# SparkFun_Qwiic_CO2_Sensor_XENSIV_PAS.net
KiCad netlist of a schematic drawn in EAGLE
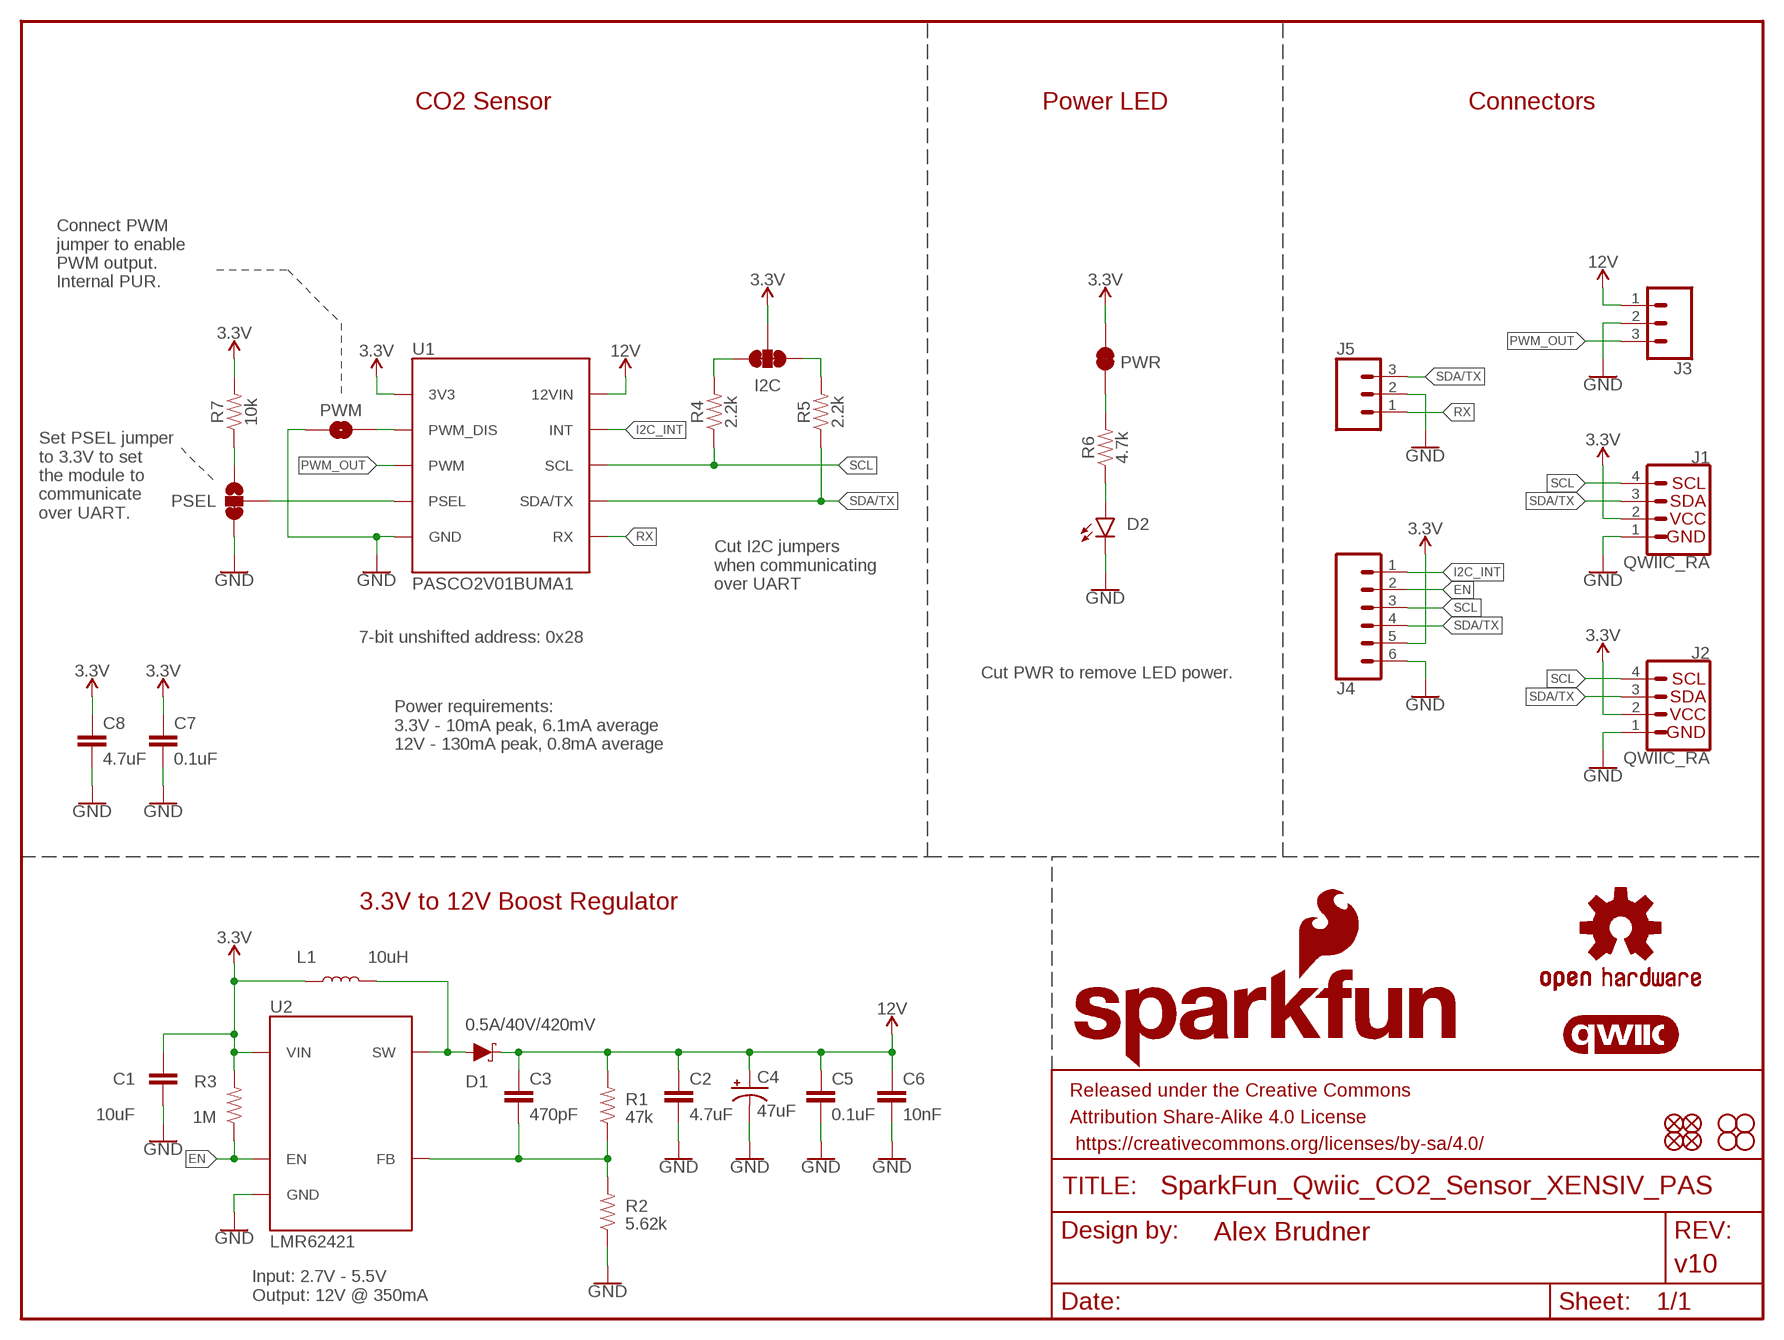
[diagram p0: schematic, sheet 1]

(export (version "E")
  (design (tool "Eeschema 10.0.6"))
  (components
    (comp (ref "C1")
      (value "10uF")
      (footprint "eagle-import:0805")
      (libsource (lib "eagle-import") (part "10UF-0805-25V-10%"))
    )
    (comp (ref "C2")
      (value "4.7uF")
      (footprint "eagle-import:0603")
      (libsource (lib "eagle-import") (part "4.7UF-0603-35V-(20%)"))
    )
    (comp (ref "C3")
      (value "470pF")
      (footprint "eagle-import:0603")
      (libsource (lib "eagle-import") (part "470PF-0603-50V-5%"))
    )
    (comp (ref "C4")
      (value "47uF")
      (footprint "eagle-import:PANASONIC_D")
      (libsource (lib "eagle-import") (part "47UF-POLAR-PANASONIC_D-35V-20%"))
    )
    (comp (ref "C5")
      (value "0.1uF")
      (footprint "eagle-import:0603")
      (libsource (lib "eagle-import") (part "0.1UF-0603-25V-5%"))
    )
    (comp (ref "C6")
      (value "10nF")
      (footprint "eagle-import:0603")
      (libsource (lib "eagle-import") (part "10NF-0603-50V-10%"))
    )
    (comp (ref "C7")
      (value "0.1uF")
      (footprint "eagle-import:0603")
      (libsource (lib "eagle-import") (part "0.1UF-0603-25V-5%"))
    )
    (comp (ref "C8")
      (value "4.7uF")
      (footprint "eagle-import:0603")
      (libsource (lib "eagle-import") (part "4.7UF-0603-35V-(20%)"))
    )
    (comp (ref "D1")
      (value "0.5A/40V/420mV")
      (footprint "eagle-import:SOD-323")
      (libsource (lib "eagle-import") (part "DIODE-SCHOTTKY-PMEG4005EJ"))
    )
    (comp (ref "D2")
      (value "LED-RED_0603-KB")
      (footprint "eagle-import:LED-0603")
      (libsource (lib "eagle-import") (part "LED-RED_0603-KB"))
    )
    (comp (ref "FD1")
      (value "FIDUCIALUFIDUCIAL")
      (footprint "eagle-import:FIDUCIAL-MICRO")
      (libsource (lib "eagle-import") (part "FIDUCIALUFIDUCIAL"))
    )
    (comp (ref "FD2")
      (value "FIDUCIALUFIDUCIAL")
      (footprint "eagle-import:FIDUCIAL-MICRO")
      (libsource (lib "eagle-import") (part "FIDUCIALUFIDUCIAL"))
    )
    (comp (ref "FD3")
      (value "FIDUCIALUFIDUCIAL")
      (footprint "eagle-import:FIDUCIAL-MICRO")
      (libsource (lib "eagle-import") (part "FIDUCIALUFIDUCIAL"))
    )
    (comp (ref "FD4")
      (value "FIDUCIALUFIDUCIAL")
      (footprint "eagle-import:FIDUCIAL-MICRO")
      (libsource (lib "eagle-import") (part "FIDUCIALUFIDUCIAL"))
    )
    (comp (ref "FRAME1")
      (value "FRAME-LETTER")
      (footprint "eagle-import:CREATIVE_COMMONS")
      (fields (field (name "DESIGNER") "Alex Brudner") (field (name "REV") "v10"))
      (libsource (lib "eagle-import") (part "FRAME-LETTER"))
    )
    (comp (ref "H1")
      (value "STAND-OFF")
      (footprint "eagle-import:STAND-OFF")
      (libsource (lib "eagle-import") (part "STAND-OFF"))
    )
    (comp (ref "H2")
      (value "STAND-OFF")
      (footprint "eagle-import:STAND-OFF")
      (libsource (lib "eagle-import") (part "STAND-OFF"))
    )
    (comp (ref "H3")
      (value "STAND-OFF")
      (footprint "eagle-import:STAND-OFF")
      (libsource (lib "eagle-import") (part "STAND-OFF"))
    )
    (comp (ref "H4")
      (value "STAND-OFF")
      (footprint "eagle-import:STAND-OFF")
      (libsource (lib "eagle-import") (part "STAND-OFF"))
    )
    (comp (ref "I2C")
      (value "JUMPER-SMT_3_2-NC_TRACE_SILK")
      (footprint "eagle-import:SMT-JUMPER_3_2-NC_TRACE_SILK")
      (libsource (lib "eagle-import") (part "JUMPER-SMT_3_2-NC_TRACE_SILK"))
    )
    (comp (ref "J1")
      (value "QWIIC_RA")
      (footprint "eagle-import:JST04_1MM_RA")
      (libsource (lib "eagle-import") (part "QWIIC_CONNECTORJS-1MM"))
    )
    (comp (ref "J2")
      (value "QWIIC_RA")
      (footprint "eagle-import:JST04_1MM_RA")
      (libsource (lib "eagle-import") (part "QWIIC_CONNECTORJS-1MM"))
    )
    (comp (ref "J3")
      (value "CONN_031X03_NO_SILK")
      (footprint "eagle-import:1X03_NO_SILK")
      (libsource (lib "eagle-import") (part "CONN_031X03_NO_SILK"))
    )
    (comp (ref "J4")
      (value "CONN_06NO_SILK_NO_POP")
      (footprint "eagle-import:1X06_NO_SILK")
      (libsource (lib "eagle-import") (part "CONN_06NO_SILK_NO_POP"))
    )
    (comp (ref "J5")
      (value "CONN_031X03_NO_SILK")
      (footprint "eagle-import:1X03_NO_SILK")
      (libsource (lib "eagle-import") (part "CONN_031X03_NO_SILK"))
    )
    (comp (ref "L1")
      (value "10uH")
      (footprint "eagle-import:0805")
      (libsource (lib "eagle-import") (part "10UH"))
    )
    (comp (ref "LOGO1")
      (value "SFE_LOGO_NAME_FLAME.1_INCH")
      (footprint "eagle-import:SFE_LOGO_NAME_FLAME_.1")
      (libsource (lib "eagle-import") (part "SFE_LOGO_NAME_FLAME.1_INCH"))
    )
    (comp (ref "LOGO2")
      (value "QWIIC_LOGO_5MM")
      (footprint "eagle-import:QWIIC_5MM")
      (libsource (lib "eagle-import") (part "QWIIC_LOGO_5MM"))
    )
    (comp (ref "LOGO3")
      (value "OSHW-LOGOMINI")
      (footprint "eagle-import:OSHW-LOGO-MINI")
      (libsource (lib "eagle-import") (part "OSHW-LOGOMINI"))
    )
    (comp (ref "PSEL")
      (value "JUMPER-SMT_3_1-NC_TRACE_SILK")
      (footprint "eagle-import:SMT-JUMPER_3_1-NC_TRACE_SILK")
      (libsource (lib "eagle-import") (part "JUMPER-SMT_3_1-NC_TRACE_SILK"))
    )
    (comp (ref "PWM")
      (value "JUMPER-SMT_2_NO_SILK")
      (footprint "eagle-import:SMT-JUMPER_2_NO_SILK")
      (libsource (lib "eagle-import") (part "JUMPER-SMT_2_NO_SILK"))
    )
    (comp (ref "PWR")
      (value "JUMPER-SMT_2_NC_TRACE_SILK")
      (footprint "eagle-import:SMT-JUMPER_2_NC_TRACE_SILK")
      (libsource (lib "eagle-import") (part "JUMPER-SMT_2_NC_TRACE_SILK"))
    )
    (comp (ref "R1")
      (value "47k")
      (footprint "eagle-import:0603")
      (libsource (lib "eagle-import") (part "47KOHM-0603-1/10W-1%"))
    )
    (comp (ref "R2")
      (value "5.62k")
      (footprint "eagle-import:0603")
      (libsource (lib "eagle-import") (part "5.62KOHM-0603-1/10W-1%"))
    )
    (comp (ref "R3")
      (value "1M")
      (footprint "eagle-import:0603")
      (libsource (lib "eagle-import") (part "1MOHM-0603-1/4W-5%"))
    )
    (comp (ref "R4")
      (value "2.2k")
      (footprint "eagle-import:0603")
      (libsource (lib "eagle-import") (part "2.2KOHM-0603-1/10W-1%"))
    )
    (comp (ref "R5")
      (value "2.2k")
      (footprint "eagle-import:0603")
      (libsource (lib "eagle-import") (part "2.2KOHM-0603-1/10W-1%"))
    )
    (comp (ref "R6")
      (value "4.7k")
      (footprint "eagle-import:0603")
      (libsource (lib "eagle-import") (part "4.7KOHM-0603-1/10W-1%"))
    )
    (comp (ref "R7")
      (value "10k")
      (footprint "eagle-import:0603")
      (libsource (lib "eagle-import") (part "10KOHM-0603-1/10W-1%"))
    )
    (comp (ref "U1")
      (value "PASCO2V01BUMA1")
      (footprint "eagle-import:LG-MLGA-14-1_Z8B00206105")
      (libsource (lib "eagle-import") (part "PASCO2V01"))
    )
    (comp (ref "U2")
      (value "LMR62421")
      (footprint "eagle-import:SOT95P280X145-5M")
      (libsource (lib "eagle-import") (part "LMR62421"))
    )
  )
  (nets
    (net (code "1") (name "3.3V") (class "Default")
      (node (ref "C1") (pin "1") (pinfunction "1_1") (pintype "passive"))
      (node (ref "C7") (pin "1") (pinfunction "1_1") (pintype "passive"))
      (node (ref "C8") (pin "1") (pinfunction "1_1") (pintype "passive"))
      (node (ref "I2C") (pin "2") (pinfunction "2_2") (pintype "passive"))
      (node (ref "J1") (pin "2") (pinfunction "2_2") (pintype "power_in"))
      (node (ref "J2") (pin "2") (pinfunction "2_2") (pintype "power_in"))
      (node (ref "J4") (pin "5") (pinfunction "5_5") (pintype "passive"))
      (node (ref "L1") (pin "1") (pinfunction "1_1") (pintype "passive"))
      (node (ref "PWR") (pin "2") (pinfunction "2_2") (pintype "passive"))
      (node (ref "R3") (pin "2") (pinfunction "2_2") (pintype "passive"))
      (node (ref "R7") (pin "2") (pinfunction "2_2") (pintype "passive"))
      (node (ref "U1") (pin "1") (pinfunction "3V3_1") (pintype "bidirectional"))
      (node (ref "U2") (pin "5") (pinfunction "VIN_5") (pintype "bidirectional"))
    )
    (net (code "2") (name "12V") (class "Default")
      (node (ref "C2") (pin "1") (pinfunction "1_1") (pintype "passive"))
      (node (ref "C3") (pin "1") (pinfunction "1_1") (pintype "passive"))
      (node (ref "C4") (pin "+") (pinfunction "+_+") (pintype "passive"))
      (node (ref "C5") (pin "1") (pinfunction "1_1") (pintype "passive"))
      (node (ref "C6") (pin "1") (pinfunction "1_1") (pintype "passive"))
      (node (ref "D1") (pin "C") (pinfunction "C_C") (pintype "passive"))
      (node (ref "J3") (pin "1") (pinfunction "1_1") (pintype "passive"))
      (node (ref "R1") (pin "2") (pinfunction "2_2") (pintype "passive"))
      (node (ref "U1") (pin "10") (pinfunction "12VIN_10") (pintype "bidirectional"))
    )
    (net (code "3") (name "EN") (class "Default")
      (node (ref "J4") (pin "2") (pinfunction "2_2") (pintype "passive"))
      (node (ref "R3") (pin "1") (pinfunction "1_1") (pintype "passive"))
      (node (ref "U2") (pin "4") (pinfunction "EN_4") (pintype "bidirectional"))
    )
    (net (code "4") (name "GND") (class "Default")
      (node (ref "C1") (pin "2") (pinfunction "2_2") (pintype "passive"))
      (node (ref "C2") (pin "2") (pinfunction "2_2") (pintype "passive"))
      (node (ref "C4") (pin "-") (pinfunction "-_-") (pintype "passive"))
      (node (ref "C5") (pin "2") (pinfunction "2_2") (pintype "passive"))
      (node (ref "C6") (pin "2") (pinfunction "2_2") (pintype "passive"))
      (node (ref "C7") (pin "2") (pinfunction "2_2") (pintype "passive"))
      (node (ref "C8") (pin "2") (pinfunction "2_2") (pintype "passive"))
      (node (ref "D2") (pin "C") (pinfunction "C_C") (pintype "passive"))
      (node (ref "J1") (pin "1") (pinfunction "1_1") (pintype "power_in"))
      (node (ref "J2") (pin "1") (pinfunction "1_1") (pintype "power_in"))
      (node (ref "J3") (pin "2") (pinfunction "2_2") (pintype "passive"))
      (node (ref "J4") (pin "6") (pinfunction "6_6") (pintype "passive"))
      (node (ref "J5") (pin "2") (pinfunction "2_2") (pintype "passive"))
      (node (ref "PSEL") (pin "3") (pinfunction "3_3") (pintype "passive"))
      (node (ref "PWM") (pin "1") (pinfunction "1_1") (pintype "passive"))
      (node (ref "R2") (pin "1") (pinfunction "1_1") (pintype "passive"))
      (node (ref "U1") (pin "11") (pinfunction "GND_11") (pintype "bidirectional"))
      (node (ref "U1") (pin "12") (pinfunction "GND_12") (pintype "bidirectional"))
      (node (ref "U1") (pin "13") (pinfunction "GND_13") (pintype "bidirectional"))
      (node (ref "U1") (pin "14") (pinfunction "GND_14") (pintype "bidirectional"))
      (node (ref "U1") (pin "6") (pinfunction "GND_6") (pintype "bidirectional"))
      (node (ref "U2") (pin "2") (pinfunction "GND_2") (pintype "bidirectional"))
    )
    (net (code "5") (name "I2C_INT") (class "Default")
      (node (ref "J4") (pin "1") (pinfunction "1_1") (pintype "passive"))
      (node (ref "U1") (pin "7") (pinfunction "INT_7") (pintype "bidirectional"))
    )
    (net (code "6") (name "Net-(D2-PadA)") (class "Default")
      (node (ref "D2") (pin "A") (pinfunction "A_A") (pintype "passive"))
      (node (ref "R6") (pin "1") (pinfunction "1_1") (pintype "passive"))
    )
    (net (code "7") (name "Net-(I2C-Pad1)") (class "Default")
      (node (ref "I2C") (pin "1") (pinfunction "1_1") (pintype "passive"))
      (node (ref "R5") (pin "2") (pinfunction "2_2") (pintype "passive"))
    )
    (net (code "8") (name "Net-(I2C-Pad3)") (class "Default")
      (node (ref "I2C") (pin "3") (pinfunction "3_3") (pintype "passive"))
      (node (ref "R4") (pin "2") (pinfunction "2_2") (pintype "passive"))
    )
    (net (code "9") (name "Net-(PSEL-Pad1)") (class "Default")
      (node (ref "PSEL") (pin "1") (pinfunction "1_1") (pintype "passive"))
      (node (ref "R7") (pin "1") (pinfunction "1_1") (pintype "passive"))
    )
    (net (code "10") (name "Net-(PWR-Pad1)") (class "Default")
      (node (ref "PWR") (pin "1") (pinfunction "1_1") (pintype "passive"))
      (node (ref "R6") (pin "2") (pinfunction "2_2") (pintype "passive"))
    )
    (net (code "11") (name "Net-(U1-PSEL)") (class "Default")
      (node (ref "PSEL") (pin "2") (pinfunction "2_2") (pintype "passive"))
      (node (ref "U1") (pin "8") (pinfunction "PSEL_8") (pintype "bidirectional"))
    )
    (net (code "12") (name "Net-(U1-PWM_DIS)") (class "Default")
      (node (ref "PWM") (pin "2") (pinfunction "2_2") (pintype "passive"))
      (node (ref "U1") (pin "5") (pinfunction "PWM_DIS_5") (pintype "bidirectional"))
    )
    (net (code "13") (name "Net-(U2-FB)") (class "Default")
      (node (ref "C3") (pin "2") (pinfunction "2_2") (pintype "passive"))
      (node (ref "R1") (pin "1") (pinfunction "1_1") (pintype "passive"))
      (node (ref "R2") (pin "2") (pinfunction "2_2") (pintype "passive"))
      (node (ref "U2") (pin "3") (pinfunction "FB_3") (pintype "bidirectional"))
    )
    (net (code "14") (name "Net-(U2-SW)") (class "Default")
      (node (ref "D1") (pin "A") (pinfunction "A_A") (pintype "passive"))
      (node (ref "L1") (pin "2") (pinfunction "2_2") (pintype "passive"))
      (node (ref "U2") (pin "1") (pinfunction "SW_1") (pintype "bidirectional"))
    )
    (net (code "15") (name "PWM_OUT") (class "Default")
      (node (ref "J3") (pin "3") (pinfunction "3_3") (pintype "passive"))
      (node (ref "U1") (pin "9") (pinfunction "PWM_9") (pintype "bidirectional"))
    )
    (net (code "16") (name "RX") (class "Default")
      (node (ref "J5") (pin "1") (pinfunction "1_1") (pintype "passive"))
      (node (ref "U1") (pin "2") (pinfunction "RX_2") (pintype "bidirectional"))
    )
    (net (code "17") (name "SCL") (class "Default")
      (node (ref "J1") (pin "4") (pinfunction "4_4") (pintype "passive"))
      (node (ref "J2") (pin "4") (pinfunction "4_4") (pintype "passive"))
      (node (ref "J4") (pin "3") (pinfunction "3_3") (pintype "passive"))
      (node (ref "R4") (pin "1") (pinfunction "1_1") (pintype "passive"))
      (node (ref "U1") (pin "3") (pinfunction "SCL_3") (pintype "bidirectional"))
    )
    (net (code "18") (name "SDA{slash}TX") (class "Default")
      (node (ref "J1") (pin "3") (pinfunction "3_3") (pintype "passive"))
      (node (ref "J2") (pin "3") (pinfunction "3_3") (pintype "passive"))
      (node (ref "J4") (pin "4") (pinfunction "4_4") (pintype "passive"))
      (node (ref "J5") (pin "3") (pinfunction "3_3") (pintype "passive"))
      (node (ref "R5") (pin "1") (pinfunction "1_1") (pintype "passive"))
      (node (ref "U1") (pin "4") (pinfunction "SDA/TX_4") (pintype "bidirectional"))
    )
  )
)
